# JacdacTactEcBc30_132.net
KiCad netlist of a schematic drawn in Altium Designer
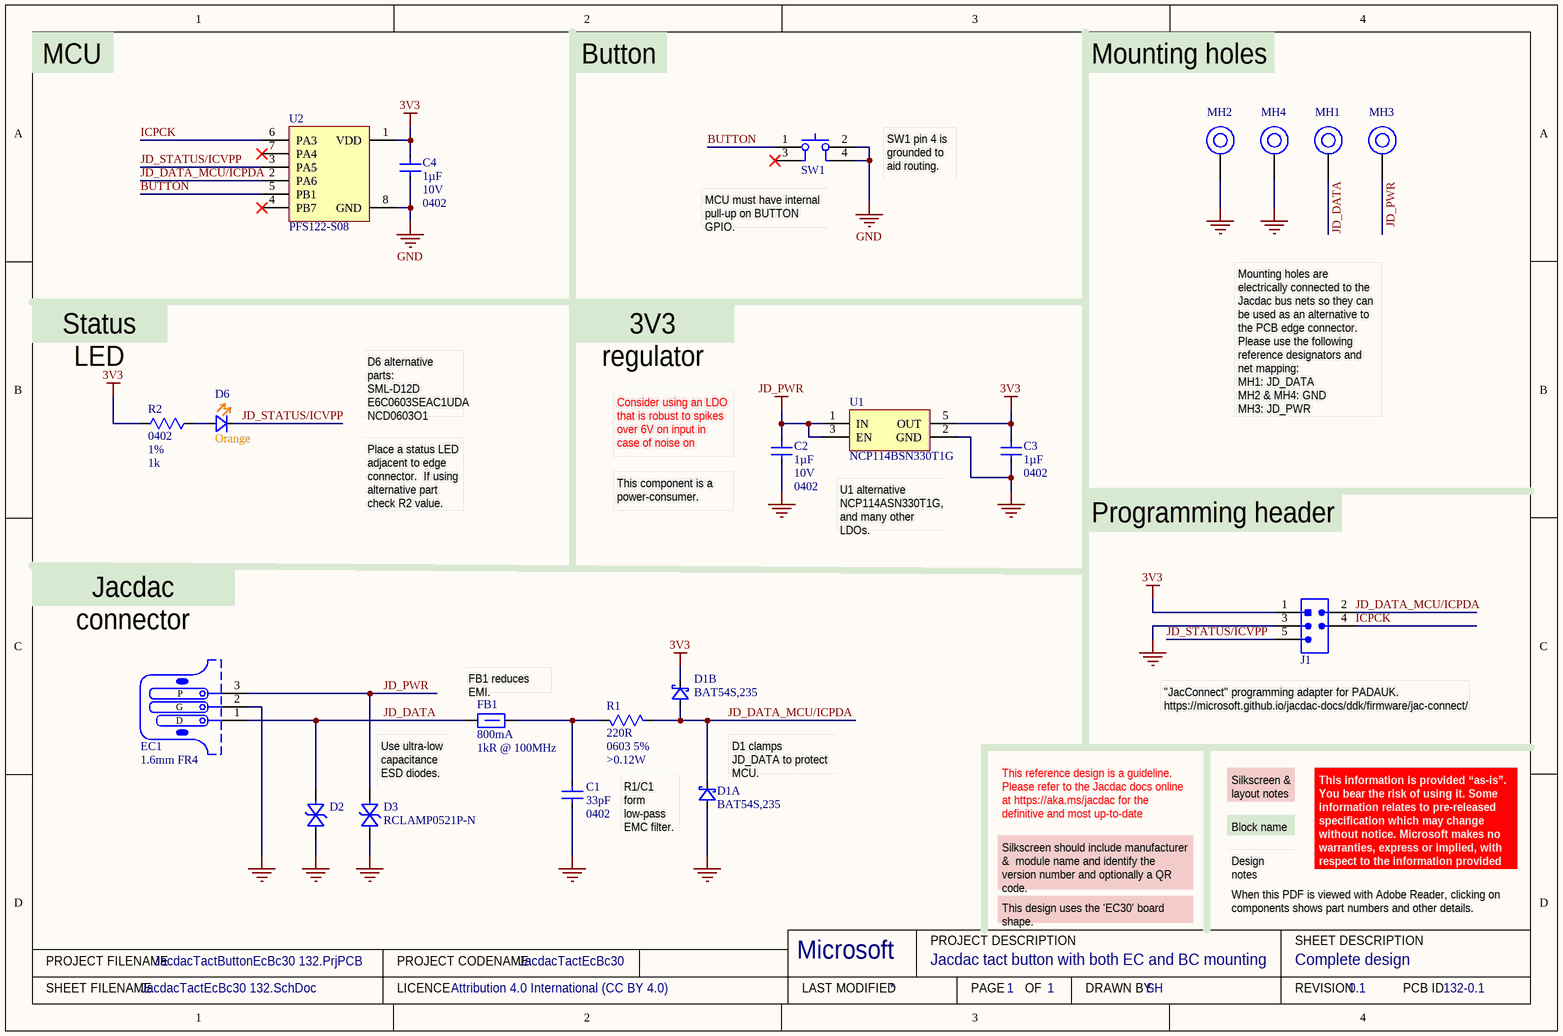
[diagram p0: JacdacTactEcBc30 132.SchDoc]

(export (version "E")
  (design (tool "Eeschema 10.0.6"))
  (components
    (comp (ref "C1")
      (value "CL05C330JB5NNNC")
      (footprint "C0402_0.55MM - without outline")
      (description "CAP CER 33PF 50V C0G/NP0 0402")
      (fields
        (field (name "MANUFACTURER") "Samsung")
        (field (name "CASE CODE (IMPERIAL)") "0402")
        (field (name "TOLERANCE") "5%")
        (field (name "CAPACITANCE") "33pF")
      )
      (libsource (lib "Samsung") (part "CL05C330JB5NNNC"))
    )
    (comp (ref "C2")
      (value "CL05A105KP5NNNC")
      (footprint "C0402_0.55MM - without outline")
      (description "CAP CER 1UF 10V X5R 0402")
      (fields
        (field (name "MANUFACTURER") "Samsung")
        (field (name "TOLERANCE") "10%")
        (field (name "CAPACITANCE") "1µF")
        (field (name "VOLTAGE RATING") "10V")
        (field (name "CASE CODE (IMPERIAL)") "0402")
        (field (name "CREATED") "DG")
        (field (name "CHECKED") "?")
      )
      (libsource (lib "Samsung") (part "CL05A105KP5NNNC"))
    )
    (comp (ref "C3")
      (value "CL05A105KP5NNNC")
      (footprint "C0402_0.55MM - without outline")
      (description "CAP CER 1UF 10V X5R 0402")
      (fields
        (field (name "MANUFACTURER") "Samsung")
        (field (name "TOLERANCE") "10%")
        (field (name "CAPACITANCE") "1µF")
        (field (name "CASE CODE (IMPERIAL)") "0402")
        (field (name "CREATED") "DG")
        (field (name "CHECKED") "?")
      )
      (libsource (lib "Samsung") (part "CL05A105KP5NNNC"))
    )
    (comp (ref "C4")
      (value "CL05A105KP5NNNC")
      (footprint "C0402_0.55MM - without outline")
      (description "CAP CER 1UF 10V X5R 0402")
      (fields
        (field (name "MANUFACTURER") "Samsung")
        (field (name "TOLERANCE") "10%")
        (field (name "CAPACITANCE") "1µF")
        (field (name "VOLTAGE RATING") "10V")
        (field (name "CASE CODE (IMPERIAL)") "0402")
        (field (name "CREATED") "DG")
        (field (name "CHECKED") "?")
      )
      (libsource (lib "Samsung") (part "CL05A105KP5NNNC"))
    )
    (comp (ref "D1")
      (value "BAT54S")
      (footprint "NXP-BAT54S-TO-236AB - without outline")
      (description "DIODE ARRAY SCHOTTKY 30V SOT23")
      (fields (field (name "MANUFACTURER") "Nexperia") (field (name "MANUFACTURER PART NUMBER") "BAT54S,235"))
      (libsource (lib "NXP") (part "BAT54S"))
    )
    (comp (ref "D2")
      (value "RCLAMP0521P-N")
      (footprint "0402:TVS 0402 - XL")
      (description "Bidirectional 5V (Max) 6V 16V 3.5A (8/20us) 0402 TVS RoHS")
      (fields
        (field (name "MANUFACTURER") "Born Semiconductor")
        (field (name "CREATED BY") "D Gakure")
        (field (name "CHECKED BY") "?")
      )
      (libsource (lib "BornSemiconductor") (part "RCLAMP0521P-N"))
    )
    (comp (ref "D3")
      (value "RCLAMP0521P-N")
      (footprint "0402:TVS 0402 - XL")
      (description "Bidirectional 5V (Max) 6V 16V 3.5A (8/20us) 0402 TVS RoHS")
      (fields
        (field (name "MANUFACTURER") "Born Semiconductor")
        (field (name "MANUFACTURER PART NUMBER") "RCLAMP0521P-N")
        (field (name "CREATED BY") "D Gakure")
        (field (name "CHECKED BY") "?")
      )
      (libsource (lib "BornSemiconductor") (part "RCLAMP0521P-N"))
    )
    (comp (ref "D6")
      (value "~")
      (footprint "0603 Orange - without outline")
      (description "LED ORANGE DIFFUSED 1608 SMD")
      (fields
        (field (name "MANUFACTURER") "Everlight Elec")
        (field (name "MANUFACTURER PART NUMBER") "19-217/S2C-AQ1R1B/3T")
        (field (name "COLOUR") "Orange")
      )
      (libsource (lib "EverlightElec") (part "19-217/S2C-AQ1R1B/3T"))
    )
    (comp (ref "EC1")
      (value "3 pin JACDAC edge connector")
      (footprint "JACDAC_edge_connector:JACDAC_EDGE_CONNECTOR_NO_TRACES_3D_PADS")
      (description "3 pin Jacdac edge connector 1.27mm pitch")
      (fields
        (field (name "MANUFACTURER PART NUMBER") "JACDAC_EDGE_CONNECTOR")
        (field (name "PCB TYPE") "1.6mm FR4")
        (field (name "CHECKED BY") "?")
        (field (name "CREATED BY") "D. Gakure")
      )
      (libsource (lib "generic-con") (part "Jacdac edge connector"))
    )
    (comp (ref "FB1")
      (value "TDK MPZ1608S102ATA00")
      (footprint "TDK MPZ1608 0.8mm - without outline")
      (description "0603 1k@100MHz 0.8A chip")
      (fields
        (field (name "TOLERANCE") "25%")
        (field (name "MANUFACTURER") "TDK")
        (field (name "CURRENT RATING") "800mA")
        (field (name "IMPEDANCE") "1kR @ 100MHz")
      )
      (libsource (lib "TDK") (part "TDK MPZ1608S102ATA00"))
    )
    (comp (ref "J1")
      (value "Hack Connect Mini 1.27 mm pitch 2-row")
      (footprint "HackConnect:HACK_CONNECT_MINI_5_X_1_27_0.559mm_TH")
      (libsource (lib "generic-con") (part "HACK_CONNECT_MINI"))
    )
    (comp (ref "MH1")
      (value "MH_7.0MMK_4.4MMC_3.1MMD_PTH")
      (footprint "MH_7.0MMK_4.4MMC_3.1MMD_PTH:MH_7.0MMK_4.4MMC_3.1MMD_PTH-SILK_D")
      (description "Mounting Hole 7.0mm keepout, 4.4mm annualar ring and 3.1mm Drill PTH")
      (libsource (lib "generic") (part "MH_7.0MMK_4.4MMC_3.1MMD_PTH"))
    )
    (comp (ref "MH2")
      (value "MH_7.0MMK_4.4MMC_3.1MMD_PTH")
      (footprint "MH_7.0MMK_4.4MMC_3.1MMD_PTH:MH_7.0MMK_4.4MMC_3.1MMD_PTH-SILK_G")
      (description "Mounting Hole 7.0mm keepout, 4.4mm annualar ring and 3.1mm Drill PTH")
      (libsource (lib "generic") (part "MH_7.0MMK_4.4MMC_3.1MMD_PTH"))
    )
    (comp (ref "MH3")
      (value "MH_7.0MMK_4.4MMC_3.1MMD_PTH")
      (footprint "MH_7.0MMK_4.4MMC_3.1MMD_PTH:MH_7.0MMK_4.4MMC_3.1MMD_PTH-SILK_P")
      (description "Mounting Hole 7.0mm keepout, 4.4mm annualar ring and 3.1mm Drill PTH")
      (libsource (lib "generic") (part "MH_7.0MMK_4.4MMC_3.1MMD_PTH"))
    )
    (comp (ref "MH4")
      (value "MH_7.0MMK_4.4MMC_3.1MMD_PTH")
      (footprint "MH_7.0MMK_4.4MMC_3.1MMD_PTH:MH_7.0MMK_4.4MMC_3.1MMD_PTH-SILK_G")
      (description "Mounting Hole 7.0mm keepout, 4.4mm annualar ring and 3.1mm Drill PTH")
      (libsource (lib "generic") (part "MH_7.0MMK_4.4MMC_3.1MMD_PTH"))
    )
    (comp (ref "R1")
      (value "220R")
      (footprint "YAGEO-0603:RC0603")
      (description "Res Thick Film 0603 220 Ohm 1% 0.1W(1/10W) ±100ppm/°C Pad SMD T/R")
      (fields
        (field (name "TOLERANCE") "1%")
        (field (name "RESISTANCE") "220R")
        (field (name "CASE/PACKAGE") "0603")
        (field (name "COMMENT 1") "5%")
        (field (name "COMMENT 2") ">0.12W")
      )
      (libsource (lib "Yageo") (part "RC0603FR-07220RL"))
    )
    (comp (ref "R2")
      (value "RC0402FR-071KL")
      (footprint "R0402 - Without outline")
      (description "RES SMD 1K OHM 1% 1/16W 0402")
      (fields
        (field (name "MANUFACTURER") "Yageo")
        (field (name "CASE CODE (IMPERIAL)") "0402")
        (field (name "TOLERANCE") "1%")
        (field (name "RESISTANCE") "1k")
        (field (name "CREATED") "D.G")
        (field (name "CHECKED") "?")
      )
      (libsource (lib "Yageo") (part "RC0402FR-071KL"))
    )
    (comp (ref "SW1")
      (value "Tact Wurth 430152050826")
      (footprint "Wurth 430152050836-WIDE")
      (description "6x6mm SPST 0.05A 12VDC SMD 260gf")
      (fields
        (field (name "MANUFACTURER") "Wurth Electronics")
        (field (name "MANUFACTURER PART NUMBER") "430152050826")
      )
      (libsource (lib "Wurth") (part "Tact Wurth 430152050826"))
    )
    (comp (ref "U1")
      (value "LDO 3.3V/300 mA")
      (footprint "ON_SEMI-SOT23-5 - without outline")
      (description "CMOS Low Dropout Regulator (LDO), 300 mA 3.3V, Non-Active Discharge, TSOP5")
      (fields
        (field (name "MANUFACTURER") "ON Semiconductor")
        (field (name "MANUFACTURER PART NUMBER") "NCP114BSN330T1G")
      )
      (libsource (lib "OnSemiconductor") (part "NCP114BSN330T1G"))
    )
    (comp (ref "U2")
      (value "PFS122-S08")
      (footprint "PADAUK-SOP-8:SOP-8")
      (description "8bit MTP MCU with 12-bit ADC")
      (fields (field (name "MANUFACTURER") "PADAUK") (field (name "MANUFACTURER PART NUMBER") "PFS122-S08"))
      (libsource (lib "PADAUK") (part "PFS122-SO8"))
    )
  )
  (nets
    (net (code "1") (name "/BUTTON") (class "Default")
      (node (ref "SW1") (pin "1") (pinfunction "1_1") (pintype "passive"))
      (node (ref "U2") (pin "5") (pinfunction "PB1_5") (pintype "passive"))
    )
    (net (code "2") (name "/ICPCK") (class "Default")
      (node (ref "J1") (pin "4") (pinfunction "SWCLK_4") (pintype "passive"))
      (node (ref "U2") (pin "6") (pinfunction "PA3_6") (pintype "passive"))
    )
    (net (code "3") (name "/JD_DATA") (class "Default")
      (node (ref "D2") (pin "1") (pinfunction "K_1") (pintype "passive"))
      (node (ref "EC1") (pin "1") (pinfunction "D_1") (pintype "passive"))
      (node (ref "FB1") (pin "1") (pinfunction "1_1") (pintype "passive"))
      (node (ref "MH1") (pin "1") (pinfunction "1_1") (pintype "passive"))
    )
    (net (code "4") (name "/JD_DATA_MCU{slash}ICPDA") (class "Default")
      (node (ref "D1") (pin "3") (pinfunction "A_3") (pintype "passive"))
      (node (ref "J1") (pin "2") (pinfunction "SWDIO_2") (pintype "passive"))
      (node (ref "R1") (pin "1") (pinfunction "1_1") (pintype "passive"))
      (node (ref "U2") (pin "2") (pinfunction "PA6_2") (pintype "passive"))
    )
    (net (code "5") (name "/JD_STATUS{slash}ICVPP") (class "Default")
      (node (ref "D6") (pin "1") (pinfunction "K_1") (pintype "passive"))
      (node (ref "J1") (pin "5") (pinfunction "RESET_5") (pintype "passive"))
      (node (ref "U2") (pin "3") (pinfunction "PA5_3") (pintype "passive"))
    )
    (net (code "6") (name "3V3") (class "Default")
      (node (ref "C3") (pin "2") (pinfunction "2_2") (pintype "passive"))
      (node (ref "C4") (pin "2") (pinfunction "2_2") (pintype "passive"))
      (node (ref "D1") (pin "2") (pinfunction "K_2") (pintype "passive"))
      (node (ref "J1") (pin "1") (pinfunction "VCC_1") (pintype "passive"))
      (node (ref "R2") (pin "2") (pinfunction "2_2") (pintype "passive"))
      (node (ref "U1") (pin "5") (pinfunction "OUT_5") (pintype "passive"))
      (node (ref "U2") (pin "1") (pinfunction "VDD_1") (pintype "passive"))
    )
    (net (code "7") (name "GND") (class "Default")
      (node (ref "C1") (pin "1") (pinfunction "1_1") (pintype "passive"))
      (node (ref "C2") (pin "1") (pinfunction "1_1") (pintype "passive"))
      (node (ref "C3") (pin "1") (pinfunction "1_1") (pintype "passive"))
      (node (ref "C4") (pin "1") (pinfunction "1_1") (pintype "passive"))
      (node (ref "D1") (pin "1") (pinfunction "A_1") (pintype "passive"))
      (node (ref "D2") (pin "2") (pinfunction "A_2") (pintype "passive"))
      (node (ref "D3") (pin "2") (pinfunction "A_2") (pintype "passive"))
      (node (ref "EC1") (pin "2") (pinfunction "G_2") (pintype "passive"))
      (node (ref "J1") (pin "3") (pinfunction "GND_3") (pintype "passive"))
      (node (ref "MH2") (pin "1") (pinfunction "1_1") (pintype "passive"))
      (node (ref "MH4") (pin "1") (pinfunction "1_1") (pintype "passive"))
      (node (ref "SW1") (pin "2") (pinfunction "2_2") (pintype "passive"))
      (node (ref "SW1") (pin "4") (pinfunction "4_4") (pintype "passive"))
      (node (ref "U1") (pin "2") (pinfunction "GND_2") (pintype "passive"))
      (node (ref "U2") (pin "8") (pinfunction "GND_8") (pintype "passive"))
    )
    (net (code "8") (name "JD_PWR") (class "Default")
      (node (ref "C2") (pin "2") (pinfunction "2_2") (pintype "passive"))
      (node (ref "D3") (pin "1") (pinfunction "K_1") (pintype "passive"))
      (node (ref "EC1") (pin "3") (pinfunction "P_3") (pintype "passive"))
      (node (ref "MH3") (pin "1") (pinfunction "1_1") (pintype "passive"))
      (node (ref "U1") (pin "1") (pinfunction "IN_1") (pintype "passive"))
      (node (ref "U1") (pin "3") (pinfunction "EN_3") (pintype "passive"))
    )
    (net (code "9") (name "Net-(C1-Pad2)") (class "Default")
      (node (ref "C1") (pin "2") (pinfunction "2_2") (pintype "passive"))
      (node (ref "FB1") (pin "2") (pinfunction "2_2") (pintype "passive"))
      (node (ref "R1") (pin "2") (pinfunction "2_2") (pintype "passive"))
    )
    (net (code "10") (name "Net-(D6-A)") (class "Default")
      (node (ref "D6") (pin "2") (pinfunction "A_2") (pintype "passive"))
      (node (ref "R2") (pin "1") (pinfunction "1_1") (pintype "passive"))
    )
    (net (code "11") (name "unconnected-(SW1-Pad3)") (class "Default")
      (node (ref "SW1") (pin "3") (pinfunction "3_3") (pintype "passive+no_connect"))
    )
    (net (code "12") (name "unconnected-(U2-PA4-Pad7)") (class "Default")
      (node (ref "U2") (pin "7") (pinfunction "PA4_7") (pintype "passive+no_connect"))
    )
    (net (code "13") (name "unconnected-(U2-PB7-Pad4)") (class "Default")
      (node (ref "U2") (pin "4") (pinfunction "PB7_4") (pintype "passive+no_connect"))
    )
  )
)
